# motor_controller_interface.net
KiCad netlist of a schematic drawn in Altium Designer
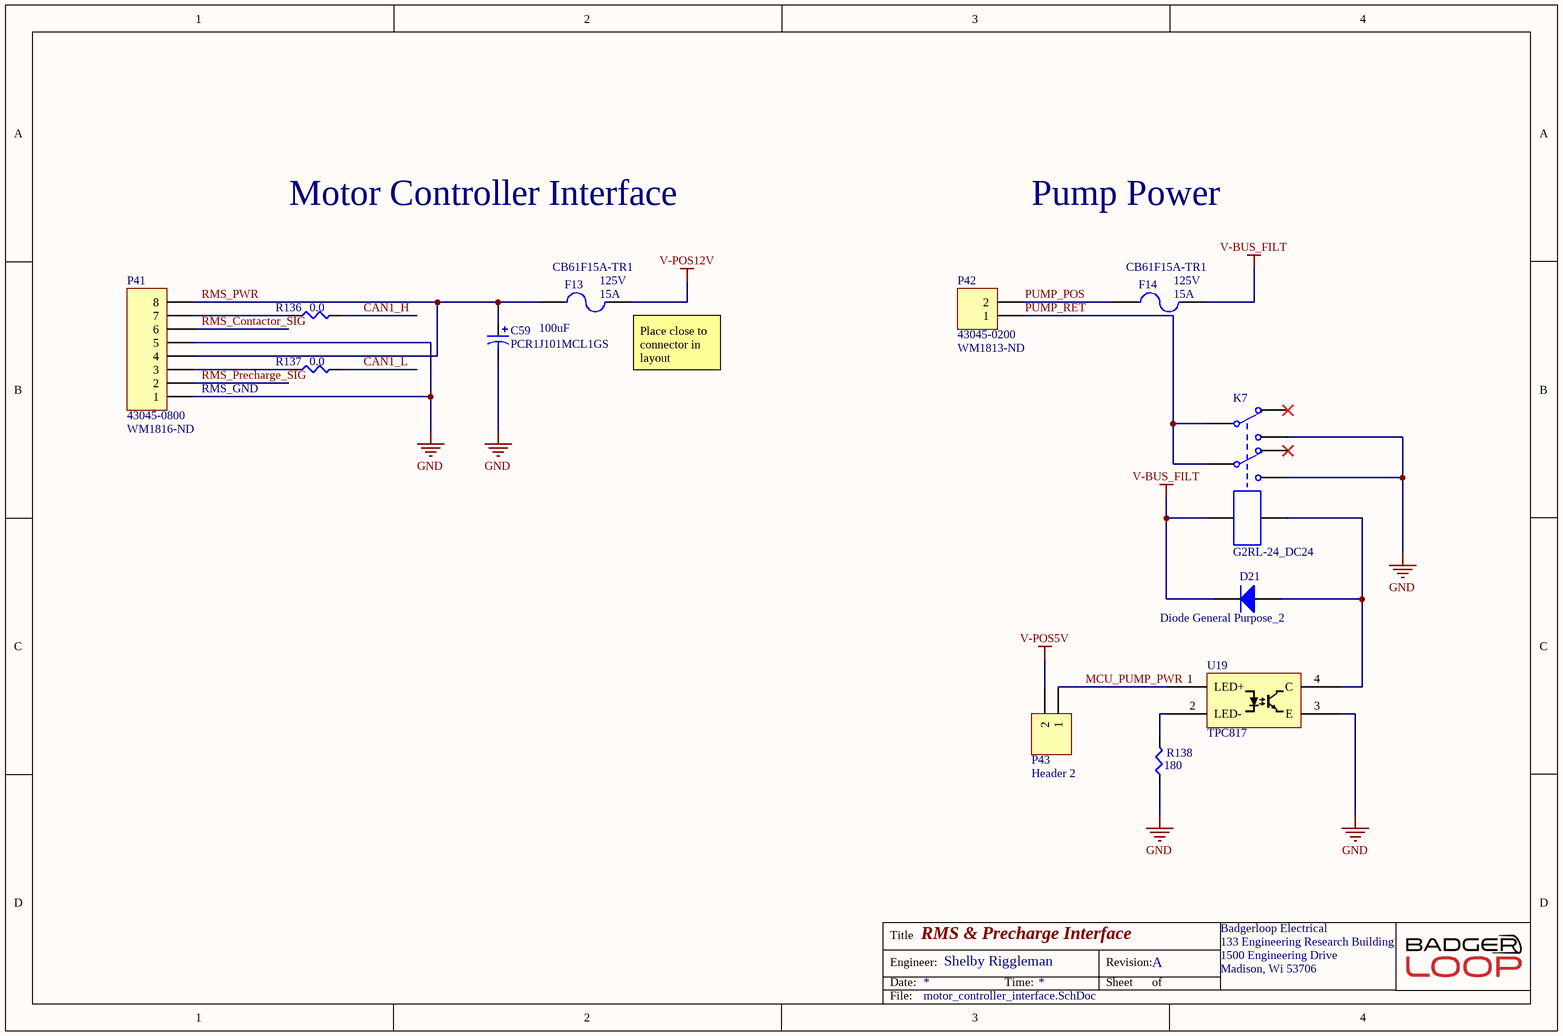
[diagram p0: motor_controller_interface.SchDoc]

(export (version "E")
  (design (tool "Eeschema 10.0.6"))
  (components
    (comp (ref "C59")
      (value "PCR1J101MCL1GS")
      (footprint "CAPAE110103X126M")
      (description "CAP ALUM POLY 100UF 20% 63V SMD")
      (fields
        (field (name "MANUFACTURER") "Nichicon")
        (field (name "CAPACITANCE") "100uF")
        (field (name "TOLERANCE") "20%")
      )
      (libsource (lib "capacitors") (part "PCR1J101MCL1GS"))
    )
    (comp (ref "D21")
      (value "Diode General Purpose_2")
      (footprint "SODFL250X110-2N")
      (description "DIODE GEN PURP 20V 350MA SOD323")
      (fields (field (name "MANUFACTURER") "Diodes Incorporated"))
      (libsource (lib "misc") (part "Diode General Purpose_2"))
    )
    (comp (ref "F13")
      (value "CB61F15A-TR1")
      (footprint "RESC6132X26N")
      (fields
        (field (name "MANUFACTURER") "Eaton")
        (field (name "CURRENT RATING") "15A")
        (field (name "VOLTAGE RATING") "125V")
      )
      (libsource (lib "misc") (part "CB61F15A-TR1"))
    )
    (comp (ref "F14")
      (value "CB61F15A-TR1")
      (footprint "RESC6132X26N")
      (fields
        (field (name "MANUFACTURER") "Eaton")
        (field (name "CURRENT RATING") "15A")
        (field (name "VOLTAGE RATING") "125V")
      )
      (libsource (lib "misc") (part "CB61F15A-TR1"))
    )
    (comp (ref "K7")
      (value "G2RL-24_DC24")
      (footprint "G2RL")
      (description "RELAY GEN PURPOSE DPDT 8A 24V")
      (fields (field (name "MANUFACTURER") "Omron") (field (name "MANUFACTURER PART NUMBER") "G2RL-24-DC24"))
      (libsource (lib "misc") (part "G2RL-24_DC24"))
    )
    (comp (ref "P41")
      (value "43045-0800")
      (footprint "430450800")
      (description "CONN HEADER R/A 8POS 3MM")
      (fields (field (name "MANUFACTURER") "Molex") (field (name "SUPPLIER PART NUMBER 1") "WM1816-ND"))
      (libsource (lib "connector") (part "43045-0800"))
    )
    (comp (ref "P42")
      (value "43045-0200")
      (footprint "430450200")
      (description "CONN HEADER R/A 2POS")
      (fields (field (name "MANUFACTURER") "Molex") (field (name "SUPPLIER PART NUMBER 1") "WM1813-ND"))
      (libsource (lib "connector") (part "43045-0200"))
    )
    (comp (ref "P43")
      (value "Header 2")
      (footprint "Pin Header 1x2 TH Pitch 2.54mm")
      (description "Header, 2-Pin")
      (fields (field (name "PUBLISHER") "Altium Limited"))
      (libsource (lib "connector") (part "Header 2"))
    )
    (comp (ref "R136")
      (value "0.0")
      (footprint "SMD-1206-RES")
      (description "RES SMD 0.0 OHM JUMPER 1/4W 1206")
      (fields (field (name "PART NUMBER") "ERJ-8GEY0R00V") (field (name "DIGI-KEY PART NUMBER") "P0.0ECT-ND"))
      (libsource (lib "resistors") (part "ERJ-8GEY0R00V"))
    )
    (comp (ref "R137")
      (value "0.0")
      (footprint "SMD-1206-RES")
      (description "RES SMD 0.0 OHM JUMPER 1/4W 1206")
      (fields (field (name "PART NUMBER") "ERJ-8GEY0R00V") (field (name "DIGI-KEY PART NUMBER") "P0.0ECT-ND"))
      (libsource (lib "resistors") (part "ERJ-8GEY0R00V"))
    )
    (comp (ref "R138")
      (value "180")
      (footprint "SMD-0805-RES")
      (description "RES SMD 180 OHM 1% 1/8W 0805")
      (fields (field (name "PART NUMBER") "ERJ-6ENF1800V") (field (name "DIGI-KEY PART NUMBER") "P180CCT-ND"))
      (libsource (lib "resistors") (part "ERJ-6ENF1800V"))
    )
    (comp (ref "U19")
      (value "TPC817")
      (footprint "SOT200P1005X328-5N")
      (description "OPTOISO 5KV TRANS 4SOP")
      (fields (field (name "MANUFACTURER") "Taiwan Semi"))
      (libsource (lib "ic") (part "TPC817"))
    )
  )
  (nets
    (net (code "1") (name "/CAN1_H") (class "Default")
      (node (ref "R136") (pin "2") (pinfunction "2_2") (pintype "passive"))
    )
    (net (code "2") (name "/CAN1_L") (class "Default")
      (node (ref "R137") (pin "2") (pinfunction "2_2") (pintype "passive"))
    )
    (net (code "3") (name "/MCU_PUMP_PWR") (class "Default")
      (node (ref "P43") (pin "1") (pinfunction "1_1") (pintype "passive"))
      (node (ref "U19") (pin "1") (pinfunction "LED+_1") (pintype "passive"))
    )
    (net (code "4") (name "/PUMP_POS") (class "Default")
      (node (ref "F14") (pin "1") (pinfunction "1_1") (pintype "passive"))
      (node (ref "P42") (pin "2") (pinfunction "2_2") (pintype "passive"))
    )
    (net (code "5") (name "/PUMP_RET") (class "Default")
      (node (ref "K7") (pin "3") (pinfunction "3_3") (pintype "passive"))
      (node (ref "K7") (pin "6") (pinfunction "6_6") (pintype "passive"))
      (node (ref "P42") (pin "1") (pinfunction "1_1") (pintype "passive"))
    )
    (net (code "6") (name "/RMS_Contactor_SIG") (class "Default")
      (node (ref "P41") (pin "6") (pinfunction "6_6") (pintype "passive"))
    )
    (net (code "7") (name "/RMS_PWR") (class "Default")
      (node (ref "C59") (pin "1") (pinfunction "1_1") (pintype "passive"))
      (node (ref "F13") (pin "1") (pinfunction "1_1") (pintype "passive"))
      (node (ref "P41") (pin "4") (pinfunction "4_4") (pintype "passive"))
      (node (ref "P41") (pin "8") (pinfunction "8_8") (pintype "passive"))
    )
    (net (code "8") (name "/RMS_Precharge_SIG") (class "Default")
      (node (ref "P41") (pin "2") (pinfunction "2_2") (pintype "passive"))
    )
    (net (code "9") (name "GND") (class "Default")
      (node (ref "C59") (pin "2") (pinfunction "2_2") (pintype "passive"))
      (node (ref "K7") (pin "4") (pinfunction "4_4") (pintype "passive"))
      (node (ref "K7") (pin "7") (pinfunction "7_7") (pintype "passive"))
      (node (ref "P41") (pin "1") (pinfunction "1_1") (pintype "passive"))
      (node (ref "P41") (pin "5") (pinfunction "5_5") (pintype "passive"))
      (node (ref "R138") (pin "1") (pinfunction "1_1") (pintype "passive"))
      (node (ref "U19") (pin "3") (pinfunction "E_3") (pintype "passive"))
    )
    (net (code "10") (name "Net-(D21-A)") (class "Default")
      (node (ref "D21") (pin "1") (pinfunction "A_1") (pintype "passive"))
      (node (ref "K7") (pin "8") (pinfunction "8_8") (pintype "passive"))
      (node (ref "U19") (pin "4") (pinfunction "C_4") (pintype "passive"))
    )
    (net (code "11") (name "Net-(P41-Pad3)") (class "Default")
      (node (ref "P41") (pin "3") (pinfunction "3_3") (pintype "passive"))
      (node (ref "R137") (pin "1") (pinfunction "1_1") (pintype "passive"))
    )
    (net (code "12") (name "Net-(P41-Pad7)") (class "Default")
      (node (ref "P41") (pin "7") (pinfunction "7_7") (pintype "passive"))
      (node (ref "R136") (pin "1") (pinfunction "1_1") (pintype "passive"))
    )
    (net (code "13") (name "Net-(U19-LED-)") (class "Default")
      (node (ref "R138") (pin "2") (pinfunction "2_2") (pintype "passive"))
      (node (ref "U19") (pin "2") (pinfunction "LED-_2") (pintype "passive"))
    )
    (net (code "14") (name "V-BUS_FILT") (class "Default")
      (node (ref "D21") (pin "2") (pinfunction "K_2") (pintype "passive"))
      (node (ref "F14") (pin "2") (pinfunction "2_2") (pintype "passive"))
      (node (ref "K7") (pin "1") (pinfunction "1_1") (pintype "passive"))
    )
    (net (code "15") (name "V-POS5V") (class "Default")
      (node (ref "P43") (pin "2") (pinfunction "2_2") (pintype "passive"))
    )
    (net (code "16") (name "V-POS12V") (class "Default")
      (node (ref "F13") (pin "2") (pinfunction "2_2") (pintype "passive"))
    )
    (net (code "17") (name "unconnected-(K7-Pad2)") (class "Default")
      (node (ref "K7") (pin "2") (pinfunction "2_2") (pintype "passive+no_connect"))
    )
    (net (code "18") (name "unconnected-(K7-Pad5)") (class "Default")
      (node (ref "K7") (pin "5") (pinfunction "5_5") (pintype "passive+no_connect"))
    )
  )
)
